# Part14_SPI_ST7789.net
KiCad netlist of a schematic drawn in Altium Designer
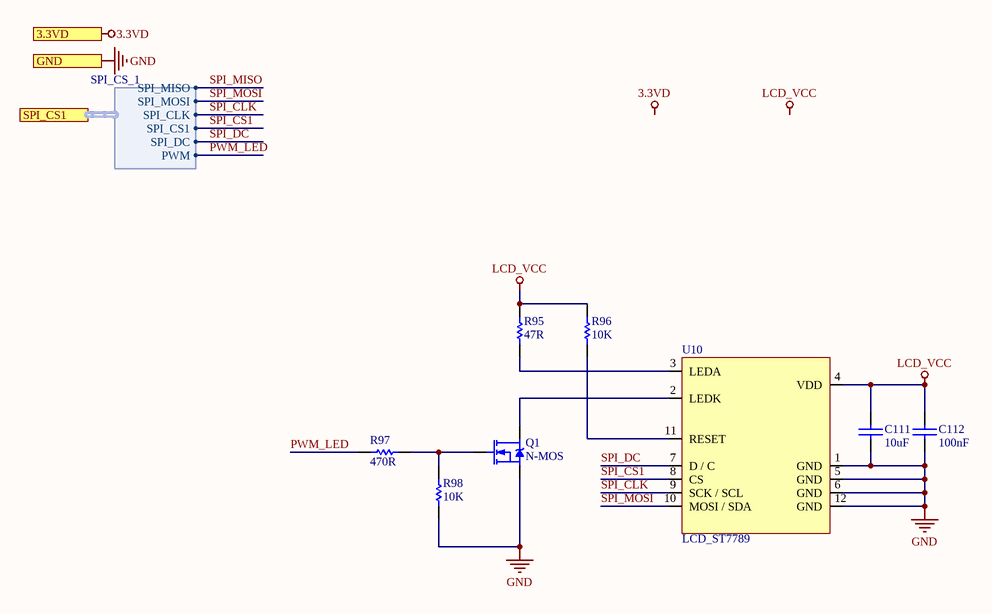
[diagram p0: Part14_SPI_ST7789.SchDoc]

(export (version "E")
  (design (tool "Eeschema 10.0.6"))
  (components
    (comp (ref "C111")
      (value "10uF")
      (footprint "0603C")
      (description "无极性电容")
      (libsource (lib "电容") (part "CAP"))
    )
    (comp (ref "C112")
      (value "100nF")
      (footprint "0603C")
      (description "无极性电容")
      (libsource (lib "电容") (part "CAP"))
    )
    (comp (ref "Q1")
      (value "N-MOS")
      (footprint "SOT23")
      (description "N沟道场效应管")
      (libsource (lib "MOS管") (part "N-MOS"))
    )
    (comp (ref "R95") (value "47R") (footprint "0603R") (libsource (lib "电阻") (part "RES")))
    (comp (ref "R96") (value "10K") (footprint "0603R") (libsource (lib "电阻") (part "RES")))
    (comp (ref "R97") (value "470R") (footprint "0603R") (libsource (lib "电阻") (part "RES")))
    (comp (ref "R98") (value "10K") (footprint "0603R") (libsource (lib "电阻") (part "RES")))
    (comp (ref "U10")
      (value "LCD_ST7789")
      (footprint "ST7789_1.3inch_IPS_TFT")
      (libsource (lib "MT7688_Lib") (part "LCD_ST7789"))
    )
  )
  (nets
    (net (code "2") (name "/PWM_LED") (class "Default")
      (node (ref "R97") (pin "1") (pinfunction "1_1") (pintype "passive"))
    )
    (net (code "3") (name "/SPI_CLK") (class "Default")
      (node (ref "U10") (pin "9") (pinfunction "SCK_/_SCL_9") (pintype "passive"))
    )
    (net (code "4") (name "/SPI_CS1") (class "Default")
      (node (ref "U10") (pin "8") (pinfunction "CS_8") (pintype "passive"))
    )
    (net (code "5") (name "/SPI_DC") (class "Default")
      (node (ref "U10") (pin "7") (pinfunction "D_/_C_7") (pintype "passive"))
    )
    (net (code "7") (name "/SPI_MOSI") (class "Default")
      (node (ref "U10") (pin "10") (pinfunction "MOSI_/_SDA_10") (pintype "passive"))
    )
    (net (code "10") (name "GND") (class "Default")
      (node (ref "C111") (pin "1") (pinfunction "1_1") (pintype "passive"))
      (node (ref "C112") (pin "1") (pinfunction "1_1") (pintype "passive"))
      (node (ref "Q1") (pin "S") (pinfunction "S_S") (pintype "passive"))
      (node (ref "R98") (pin "1") (pinfunction "1_1") (pintype "passive"))
      (node (ref "U10") (pin "1") (pinfunction "GND_1") (pintype "passive"))
      (node (ref "U10") (pin "12") (pinfunction "GND_12") (pintype "passive"))
      (node (ref "U10") (pin "5") (pinfunction "GND_5") (pintype "passive"))
      (node (ref "U10") (pin "6") (pinfunction "GND_6") (pintype "passive"))
    )
    (net (code "11") (name "LCD_VCC") (class "Default")
      (node (ref "C111") (pin "2") (pinfunction "2_2") (pintype "passive"))
      (node (ref "C112") (pin "2") (pinfunction "2_2") (pintype "passive"))
      (node (ref "R95") (pin "2") (pinfunction "2_2") (pintype "passive"))
      (node (ref "R96") (pin "2") (pinfunction "2_2") (pintype "passive"))
      (node (ref "U10") (pin "4") (pinfunction "VDD_4") (pintype "passive"))
    )
    (net (code "12") (name "Net-(Q1-PadG)") (class "Default")
      (node (ref "Q1") (pin "G") (pinfunction "G_G") (pintype "passive"))
      (node (ref "R97") (pin "2") (pinfunction "2_2") (pintype "passive"))
      (node (ref "R98") (pin "2") (pinfunction "2_2") (pintype "passive"))
    )
    (net (code "13") (name "Net-(U10-LEDA)") (class "Default")
      (node (ref "R95") (pin "1") (pinfunction "1_1") (pintype "passive"))
      (node (ref "U10") (pin "3") (pinfunction "LEDA_3") (pintype "passive"))
    )
    (net (code "14") (name "Net-(U10-LEDK)") (class "Default")
      (node (ref "Q1") (pin "D") (pinfunction "D_D") (pintype "passive"))
      (node (ref "U10") (pin "2") (pinfunction "LEDK_2") (pintype "passive"))
    )
    (net (code "15") (name "Net-(U10-RESET)") (class "Default")
      (node (ref "R96") (pin "1") (pinfunction "1_1") (pintype "passive"))
      (node (ref "U10") (pin "11") (pinfunction "RESET_11") (pintype "passive"))
    )
  )
)
